# FF0881SA1.net
KiCad netlist of a schematic drawn in EAGLE
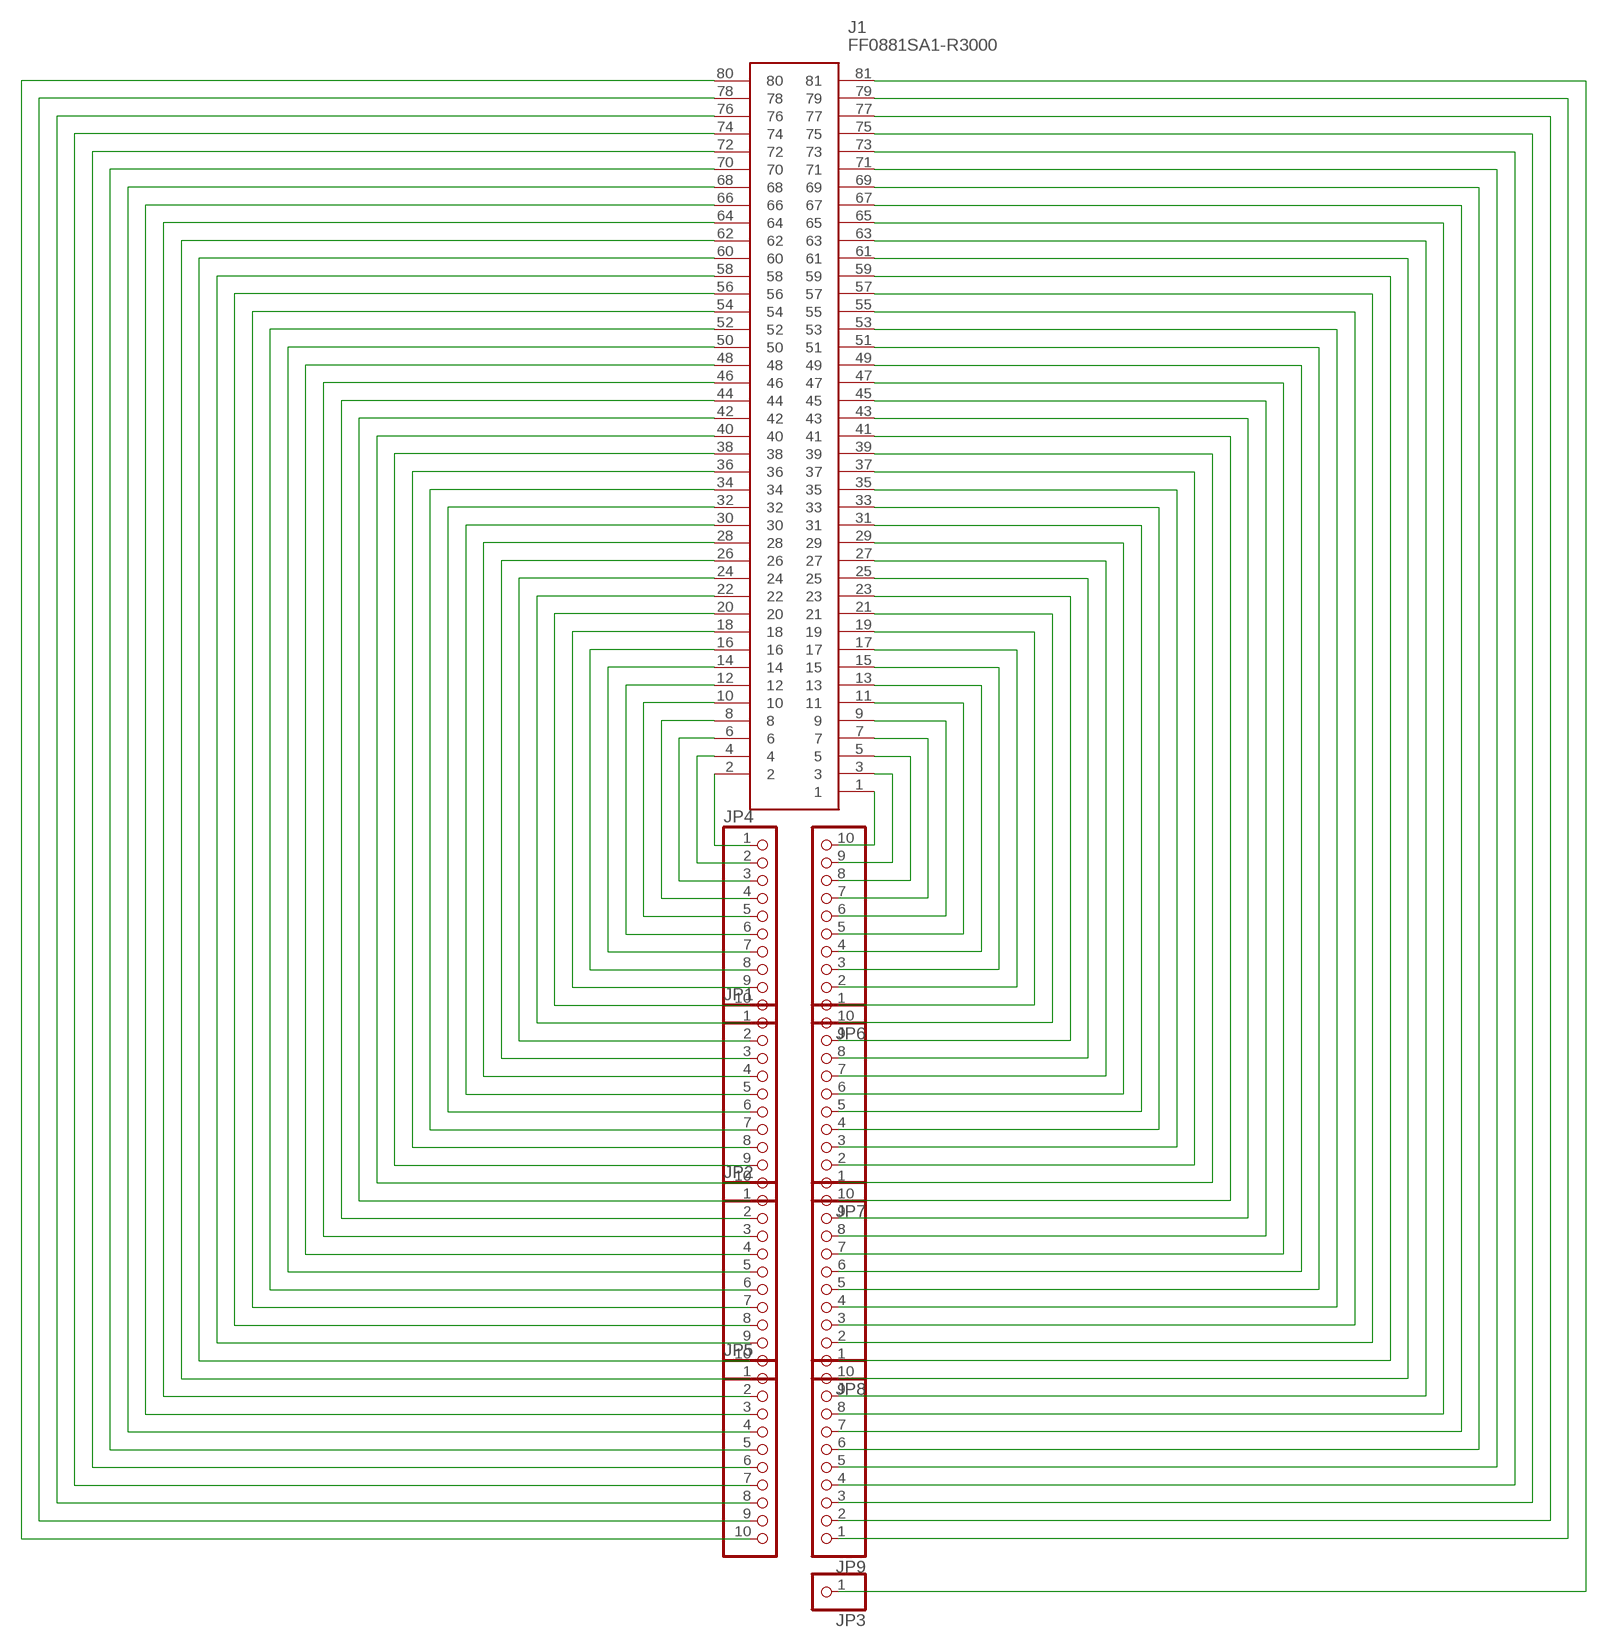
[diagram p0: schematic, sheet 1]

(export (version "E")
  (design (tool "Eeschema 10.0.6"))
  (components
    (comp (ref "J1")
      (value "FF0881SA1-R3000")
      (footprint "eagle-import:FF0881SA1R3000")
      (fields (field (name "MOUSER_PART_NUMBER") "656-FF0881SA1-R3000"))
      (libsource (lib "eagle-import") (part "FF0881SA1-R3000"))
    )
    (comp (ref "JP1")
      (value "PINHD-1X10")
      (footprint "eagle-import:1X10")
      (libsource (lib "eagle-import") (part "PINHD-1X10"))
    )
    (comp (ref "JP2")
      (value "PINHD-1X10")
      (footprint "eagle-import:1X10")
      (libsource (lib "eagle-import") (part "PINHD-1X10"))
    )
    (comp (ref "JP3")
      (value "PINHD-1X1")
      (footprint "eagle-import:1X01")
      (libsource (lib "eagle-import") (part "PINHD-1X1"))
    )
    (comp (ref "JP4")
      (value "PINHD-1X10")
      (footprint "eagle-import:1X10")
      (libsource (lib "eagle-import") (part "PINHD-1X10"))
    )
    (comp (ref "JP5")
      (value "PINHD-1X10")
      (footprint "eagle-import:1X10")
      (libsource (lib "eagle-import") (part "PINHD-1X10"))
    )
    (comp (ref "JP6")
      (value "PINHD-1X10")
      (footprint "eagle-import:1X10")
      (libsource (lib "eagle-import") (part "PINHD-1X10"))
    )
    (comp (ref "JP7")
      (value "PINHD-1X10")
      (footprint "eagle-import:1X10")
      (libsource (lib "eagle-import") (part "PINHD-1X10"))
    )
    (comp (ref "JP8")
      (value "PINHD-1X10")
      (footprint "eagle-import:1X10")
      (libsource (lib "eagle-import") (part "PINHD-1X10"))
    )
    (comp (ref "JP9")
      (value "PINHD-1X10")
      (footprint "eagle-import:1X10")
      (libsource (lib "eagle-import") (part "PINHD-1X10"))
    )
  )
  (nets
    (net (code "1") (name "Net-(J1-Pad1)") (class "Default")
      (node (ref "J1") (pin "1") (pinfunction "1_1") (pintype "bidirectional"))
      (node (ref "JP6") (pin "10") (pinfunction "10_10") (pintype "passive"))
    )
    (net (code "2") (name "Net-(J1-Pad2)") (class "Default")
      (node (ref "J1") (pin "2") (pinfunction "2_2") (pintype "bidirectional"))
      (node (ref "JP4") (pin "1") (pinfunction "1_1") (pintype "passive"))
    )
    (net (code "3") (name "Net-(J1-Pad3)") (class "Default")
      (node (ref "J1") (pin "3") (pinfunction "3_3") (pintype "bidirectional"))
      (node (ref "JP6") (pin "9") (pinfunction "9_9") (pintype "passive"))
    )
    (net (code "4") (name "Net-(J1-Pad4)") (class "Default")
      (node (ref "J1") (pin "4") (pinfunction "4_4") (pintype "bidirectional"))
      (node (ref "JP4") (pin "2") (pinfunction "2_2") (pintype "passive"))
    )
    (net (code "5") (name "Net-(J1-Pad5)") (class "Default")
      (node (ref "J1") (pin "5") (pinfunction "5_5") (pintype "bidirectional"))
      (node (ref "JP6") (pin "8") (pinfunction "8_8") (pintype "passive"))
    )
    (net (code "6") (name "Net-(J1-Pad6)") (class "Default")
      (node (ref "J1") (pin "6") (pinfunction "6_6") (pintype "bidirectional"))
      (node (ref "JP4") (pin "3") (pinfunction "3_3") (pintype "passive"))
    )
    (net (code "7") (name "Net-(J1-Pad7)") (class "Default")
      (node (ref "J1") (pin "7") (pinfunction "7_7") (pintype "bidirectional"))
      (node (ref "JP6") (pin "7") (pinfunction "7_7") (pintype "passive"))
    )
    (net (code "8") (name "Net-(J1-Pad8)") (class "Default")
      (node (ref "J1") (pin "8") (pinfunction "8_8") (pintype "bidirectional"))
      (node (ref "JP4") (pin "4") (pinfunction "4_4") (pintype "passive"))
    )
    (net (code "9") (name "Net-(J1-Pad9)") (class "Default")
      (node (ref "J1") (pin "9") (pinfunction "9_9") (pintype "bidirectional"))
      (node (ref "JP6") (pin "6") (pinfunction "6_6") (pintype "passive"))
    )
    (net (code "10") (name "Net-(J1-Pad10)") (class "Default")
      (node (ref "J1") (pin "10") (pinfunction "10_10") (pintype "bidirectional"))
      (node (ref "JP4") (pin "5") (pinfunction "5_5") (pintype "passive"))
    )
    (net (code "11") (name "Net-(J1-Pad11)") (class "Default")
      (node (ref "J1") (pin "11") (pinfunction "11_11") (pintype "bidirectional"))
      (node (ref "JP6") (pin "5") (pinfunction "5_5") (pintype "passive"))
    )
    (net (code "12") (name "Net-(J1-Pad12)") (class "Default")
      (node (ref "J1") (pin "12") (pinfunction "12_12") (pintype "bidirectional"))
      (node (ref "JP4") (pin "6") (pinfunction "6_6") (pintype "passive"))
    )
    (net (code "13") (name "Net-(J1-Pad13)") (class "Default")
      (node (ref "J1") (pin "13") (pinfunction "13_13") (pintype "bidirectional"))
      (node (ref "JP6") (pin "4") (pinfunction "4_4") (pintype "passive"))
    )
    (net (code "14") (name "Net-(J1-Pad14)") (class "Default")
      (node (ref "J1") (pin "14") (pinfunction "14_14") (pintype "bidirectional"))
      (node (ref "JP4") (pin "7") (pinfunction "7_7") (pintype "passive"))
    )
    (net (code "15") (name "Net-(J1-Pad15)") (class "Default")
      (node (ref "J1") (pin "15") (pinfunction "15_15") (pintype "bidirectional"))
      (node (ref "JP6") (pin "3") (pinfunction "3_3") (pintype "passive"))
    )
    (net (code "16") (name "Net-(J1-Pad16)") (class "Default")
      (node (ref "J1") (pin "16") (pinfunction "16_16") (pintype "bidirectional"))
      (node (ref "JP4") (pin "8") (pinfunction "8_8") (pintype "passive"))
    )
    (net (code "17") (name "Net-(J1-Pad17)") (class "Default")
      (node (ref "J1") (pin "17") (pinfunction "17_17") (pintype "bidirectional"))
      (node (ref "JP6") (pin "2") (pinfunction "2_2") (pintype "passive"))
    )
    (net (code "18") (name "Net-(J1-Pad18)") (class "Default")
      (node (ref "J1") (pin "18") (pinfunction "18_18") (pintype "bidirectional"))
      (node (ref "JP4") (pin "9") (pinfunction "9_9") (pintype "passive"))
    )
    (net (code "19") (name "Net-(J1-Pad19)") (class "Default")
      (node (ref "J1") (pin "19") (pinfunction "19_19") (pintype "bidirectional"))
      (node (ref "JP6") (pin "1") (pinfunction "1_1") (pintype "passive"))
    )
    (net (code "20") (name "Net-(J1-Pad20)") (class "Default")
      (node (ref "J1") (pin "20") (pinfunction "20_20") (pintype "bidirectional"))
      (node (ref "JP4") (pin "10") (pinfunction "10_10") (pintype "passive"))
    )
    (net (code "21") (name "Net-(J1-Pad21)") (class "Default")
      (node (ref "J1") (pin "21") (pinfunction "21_21") (pintype "bidirectional"))
      (node (ref "JP7") (pin "10") (pinfunction "10_10") (pintype "passive"))
    )
    (net (code "22") (name "Net-(J1-Pad22)") (class "Default")
      (node (ref "J1") (pin "22") (pinfunction "22_22") (pintype "bidirectional"))
      (node (ref "JP1") (pin "1") (pinfunction "1_1") (pintype "passive"))
    )
    (net (code "23") (name "Net-(J1-Pad23)") (class "Default")
      (node (ref "J1") (pin "23") (pinfunction "23_23") (pintype "bidirectional"))
      (node (ref "JP7") (pin "9") (pinfunction "9_9") (pintype "passive"))
    )
    (net (code "24") (name "Net-(J1-Pad24)") (class "Default")
      (node (ref "J1") (pin "24") (pinfunction "24_24") (pintype "bidirectional"))
      (node (ref "JP1") (pin "2") (pinfunction "2_2") (pintype "passive"))
    )
    (net (code "25") (name "Net-(J1-Pad25)") (class "Default")
      (node (ref "J1") (pin "25") (pinfunction "25_25") (pintype "bidirectional"))
      (node (ref "JP7") (pin "8") (pinfunction "8_8") (pintype "passive"))
    )
    (net (code "26") (name "Net-(J1-Pad26)") (class "Default")
      (node (ref "J1") (pin "26") (pinfunction "26_26") (pintype "bidirectional"))
      (node (ref "JP1") (pin "3") (pinfunction "3_3") (pintype "passive"))
    )
    (net (code "27") (name "Net-(J1-Pad27)") (class "Default")
      (node (ref "J1") (pin "27") (pinfunction "27_27") (pintype "bidirectional"))
      (node (ref "JP7") (pin "7") (pinfunction "7_7") (pintype "passive"))
    )
    (net (code "28") (name "Net-(J1-Pad28)") (class "Default")
      (node (ref "J1") (pin "28") (pinfunction "28_28") (pintype "bidirectional"))
      (node (ref "JP1") (pin "4") (pinfunction "4_4") (pintype "passive"))
    )
    (net (code "29") (name "Net-(J1-Pad29)") (class "Default")
      (node (ref "J1") (pin "29") (pinfunction "29_29") (pintype "bidirectional"))
      (node (ref "JP7") (pin "6") (pinfunction "6_6") (pintype "passive"))
    )
    (net (code "30") (name "Net-(J1-Pad30)") (class "Default")
      (node (ref "J1") (pin "30") (pinfunction "30_30") (pintype "bidirectional"))
      (node (ref "JP1") (pin "5") (pinfunction "5_5") (pintype "passive"))
    )
    (net (code "31") (name "Net-(J1-Pad31)") (class "Default")
      (node (ref "J1") (pin "31") (pinfunction "31_31") (pintype "bidirectional"))
      (node (ref "JP7") (pin "5") (pinfunction "5_5") (pintype "passive"))
    )
    (net (code "32") (name "Net-(J1-Pad32)") (class "Default")
      (node (ref "J1") (pin "32") (pinfunction "32_32") (pintype "bidirectional"))
      (node (ref "JP1") (pin "6") (pinfunction "6_6") (pintype "passive"))
    )
    (net (code "33") (name "Net-(J1-Pad33)") (class "Default")
      (node (ref "J1") (pin "33") (pinfunction "33_33") (pintype "bidirectional"))
      (node (ref "JP7") (pin "4") (pinfunction "4_4") (pintype "passive"))
    )
    (net (code "34") (name "Net-(J1-Pad34)") (class "Default")
      (node (ref "J1") (pin "34") (pinfunction "34_34") (pintype "bidirectional"))
      (node (ref "JP1") (pin "7") (pinfunction "7_7") (pintype "passive"))
    )
    (net (code "35") (name "Net-(J1-Pad35)") (class "Default")
      (node (ref "J1") (pin "35") (pinfunction "35_35") (pintype "bidirectional"))
      (node (ref "JP7") (pin "3") (pinfunction "3_3") (pintype "passive"))
    )
    (net (code "36") (name "Net-(J1-Pad36)") (class "Default")
      (node (ref "J1") (pin "36") (pinfunction "36_36") (pintype "bidirectional"))
      (node (ref "JP1") (pin "8") (pinfunction "8_8") (pintype "passive"))
    )
    (net (code "37") (name "Net-(J1-Pad37)") (class "Default")
      (node (ref "J1") (pin "37") (pinfunction "37_37") (pintype "bidirectional"))
      (node (ref "JP7") (pin "2") (pinfunction "2_2") (pintype "passive"))
    )
    (net (code "38") (name "Net-(J1-Pad38)") (class "Default")
      (node (ref "J1") (pin "38") (pinfunction "38_38") (pintype "bidirectional"))
      (node (ref "JP1") (pin "9") (pinfunction "9_9") (pintype "passive"))
    )
    (net (code "39") (name "Net-(J1-Pad39)") (class "Default")
      (node (ref "J1") (pin "39") (pinfunction "39_39") (pintype "bidirectional"))
      (node (ref "JP7") (pin "1") (pinfunction "1_1") (pintype "passive"))
    )
    (net (code "40") (name "Net-(J1-Pad40)") (class "Default")
      (node (ref "J1") (pin "40") (pinfunction "40_40") (pintype "bidirectional"))
      (node (ref "JP1") (pin "10") (pinfunction "10_10") (pintype "passive"))
    )
    (net (code "41") (name "Net-(J1-Pad41)") (class "Default")
      (node (ref "J1") (pin "41") (pinfunction "41_41") (pintype "bidirectional"))
      (node (ref "JP8") (pin "10") (pinfunction "10_10") (pintype "passive"))
    )
    (net (code "42") (name "Net-(J1-Pad42)") (class "Default")
      (node (ref "J1") (pin "42") (pinfunction "42_42") (pintype "bidirectional"))
      (node (ref "JP2") (pin "1") (pinfunction "1_1") (pintype "passive"))
    )
    (net (code "43") (name "Net-(J1-Pad43)") (class "Default")
      (node (ref "J1") (pin "43") (pinfunction "43_43") (pintype "bidirectional"))
      (node (ref "JP8") (pin "9") (pinfunction "9_9") (pintype "passive"))
    )
    (net (code "44") (name "Net-(J1-Pad44)") (class "Default")
      (node (ref "J1") (pin "44") (pinfunction "44_44") (pintype "bidirectional"))
      (node (ref "JP2") (pin "2") (pinfunction "2_2") (pintype "passive"))
    )
    (net (code "45") (name "Net-(J1-Pad45)") (class "Default")
      (node (ref "J1") (pin "45") (pinfunction "45_45") (pintype "bidirectional"))
      (node (ref "JP8") (pin "8") (pinfunction "8_8") (pintype "passive"))
    )
    (net (code "46") (name "Net-(J1-Pad46)") (class "Default")
      (node (ref "J1") (pin "46") (pinfunction "46_46") (pintype "bidirectional"))
      (node (ref "JP2") (pin "3") (pinfunction "3_3") (pintype "passive"))
    )
    (net (code "47") (name "Net-(J1-Pad47)") (class "Default")
      (node (ref "J1") (pin "47") (pinfunction "47_47") (pintype "bidirectional"))
      (node (ref "JP8") (pin "7") (pinfunction "7_7") (pintype "passive"))
    )
    (net (code "48") (name "Net-(J1-Pad48)") (class "Default")
      (node (ref "J1") (pin "48") (pinfunction "48_48") (pintype "bidirectional"))
      (node (ref "JP2") (pin "4") (pinfunction "4_4") (pintype "passive"))
    )
    (net (code "49") (name "Net-(J1-Pad49)") (class "Default")
      (node (ref "J1") (pin "49") (pinfunction "49_49") (pintype "bidirectional"))
      (node (ref "JP8") (pin "6") (pinfunction "6_6") (pintype "passive"))
    )
    (net (code "50") (name "Net-(J1-Pad50)") (class "Default")
      (node (ref "J1") (pin "50") (pinfunction "50_50") (pintype "bidirectional"))
      (node (ref "JP2") (pin "5") (pinfunction "5_5") (pintype "passive"))
    )
    (net (code "51") (name "Net-(J1-Pad51)") (class "Default")
      (node (ref "J1") (pin "51") (pinfunction "51_51") (pintype "bidirectional"))
      (node (ref "JP8") (pin "5") (pinfunction "5_5") (pintype "passive"))
    )
    (net (code "52") (name "Net-(J1-Pad52)") (class "Default")
      (node (ref "J1") (pin "52") (pinfunction "52_52") (pintype "bidirectional"))
      (node (ref "JP2") (pin "6") (pinfunction "6_6") (pintype "passive"))
    )
    (net (code "53") (name "Net-(J1-Pad53)") (class "Default")
      (node (ref "J1") (pin "53") (pinfunction "53_53") (pintype "bidirectional"))
      (node (ref "JP8") (pin "4") (pinfunction "4_4") (pintype "passive"))
    )
    (net (code "54") (name "Net-(J1-Pad54)") (class "Default")
      (node (ref "J1") (pin "54") (pinfunction "54_54") (pintype "bidirectional"))
      (node (ref "JP2") (pin "7") (pinfunction "7_7") (pintype "passive"))
    )
    (net (code "55") (name "Net-(J1-Pad55)") (class "Default")
      (node (ref "J1") (pin "55") (pinfunction "55_55") (pintype "bidirectional"))
      (node (ref "JP8") (pin "3") (pinfunction "3_3") (pintype "passive"))
    )
    (net (code "56") (name "Net-(J1-Pad56)") (class "Default")
      (node (ref "J1") (pin "56") (pinfunction "56_56") (pintype "bidirectional"))
      (node (ref "JP2") (pin "8") (pinfunction "8_8") (pintype "passive"))
    )
    (net (code "57") (name "Net-(J1-Pad57)") (class "Default")
      (node (ref "J1") (pin "57") (pinfunction "57_57") (pintype "bidirectional"))
      (node (ref "JP8") (pin "2") (pinfunction "2_2") (pintype "passive"))
    )
    (net (code "58") (name "Net-(J1-Pad58)") (class "Default")
      (node (ref "J1") (pin "58") (pinfunction "58_58") (pintype "bidirectional"))
      (node (ref "JP2") (pin "9") (pinfunction "9_9") (pintype "passive"))
    )
    (net (code "59") (name "Net-(J1-Pad59)") (class "Default")
      (node (ref "J1") (pin "59") (pinfunction "59_59") (pintype "bidirectional"))
      (node (ref "JP8") (pin "1") (pinfunction "1_1") (pintype "passive"))
    )
    (net (code "60") (name "Net-(J1-Pad60)") (class "Default")
      (node (ref "J1") (pin "60") (pinfunction "60_60") (pintype "bidirectional"))
      (node (ref "JP2") (pin "10") (pinfunction "10_10") (pintype "passive"))
    )
    (net (code "61") (name "Net-(J1-Pad61)") (class "Default")
      (node (ref "J1") (pin "61") (pinfunction "61_61") (pintype "bidirectional"))
      (node (ref "JP9") (pin "10") (pinfunction "10_10") (pintype "passive"))
    )
    (net (code "62") (name "Net-(J1-Pad62)") (class "Default")
      (node (ref "J1") (pin "62") (pinfunction "62_62") (pintype "bidirectional"))
      (node (ref "JP5") (pin "1") (pinfunction "1_1") (pintype "passive"))
    )
    (net (code "63") (name "Net-(J1-Pad63)") (class "Default")
      (node (ref "J1") (pin "63") (pinfunction "63_63") (pintype "bidirectional"))
      (node (ref "JP9") (pin "9") (pinfunction "9_9") (pintype "passive"))
    )
    (net (code "64") (name "Net-(J1-Pad64)") (class "Default")
      (node (ref "J1") (pin "64") (pinfunction "64_64") (pintype "bidirectional"))
      (node (ref "JP5") (pin "2") (pinfunction "2_2") (pintype "passive"))
    )
    (net (code "65") (name "Net-(J1-Pad65)") (class "Default")
      (node (ref "J1") (pin "65") (pinfunction "65_65") (pintype "bidirectional"))
      (node (ref "JP9") (pin "8") (pinfunction "8_8") (pintype "passive"))
    )
    (net (code "66") (name "Net-(J1-Pad66)") (class "Default")
      (node (ref "J1") (pin "66") (pinfunction "66_66") (pintype "bidirectional"))
      (node (ref "JP5") (pin "3") (pinfunction "3_3") (pintype "passive"))
    )
    (net (code "67") (name "Net-(J1-Pad67)") (class "Default")
      (node (ref "J1") (pin "67") (pinfunction "67_67") (pintype "bidirectional"))
      (node (ref "JP9") (pin "7") (pinfunction "7_7") (pintype "passive"))
    )
    (net (code "68") (name "Net-(J1-Pad68)") (class "Default")
      (node (ref "J1") (pin "68") (pinfunction "68_68") (pintype "bidirectional"))
      (node (ref "JP5") (pin "4") (pinfunction "4_4") (pintype "passive"))
    )
    (net (code "69") (name "Net-(J1-Pad69)") (class "Default")
      (node (ref "J1") (pin "69") (pinfunction "69_69") (pintype "bidirectional"))
      (node (ref "JP9") (pin "6") (pinfunction "6_6") (pintype "passive"))
    )
    (net (code "70") (name "Net-(J1-Pad70)") (class "Default")
      (node (ref "J1") (pin "70") (pinfunction "70_70") (pintype "bidirectional"))
      (node (ref "JP5") (pin "5") (pinfunction "5_5") (pintype "passive"))
    )
    (net (code "71") (name "Net-(J1-Pad71)") (class "Default")
      (node (ref "J1") (pin "71") (pinfunction "71_71") (pintype "bidirectional"))
      (node (ref "JP9") (pin "5") (pinfunction "5_5") (pintype "passive"))
    )
    (net (code "72") (name "Net-(J1-Pad72)") (class "Default")
      (node (ref "J1") (pin "72") (pinfunction "72_72") (pintype "bidirectional"))
      (node (ref "JP5") (pin "6") (pinfunction "6_6") (pintype "passive"))
    )
    (net (code "73") (name "Net-(J1-Pad73)") (class "Default")
      (node (ref "J1") (pin "73") (pinfunction "73_73") (pintype "bidirectional"))
      (node (ref "JP9") (pin "4") (pinfunction "4_4") (pintype "passive"))
    )
    (net (code "74") (name "Net-(J1-Pad74)") (class "Default")
      (node (ref "J1") (pin "74") (pinfunction "74_74") (pintype "bidirectional"))
      (node (ref "JP5") (pin "7") (pinfunction "7_7") (pintype "passive"))
    )
    (net (code "75") (name "Net-(J1-Pad75)") (class "Default")
      (node (ref "J1") (pin "75") (pinfunction "75_75") (pintype "bidirectional"))
      (node (ref "JP9") (pin "3") (pinfunction "3_3") (pintype "passive"))
    )
    (net (code "76") (name "Net-(J1-Pad76)") (class "Default")
      (node (ref "J1") (pin "76") (pinfunction "76_76") (pintype "bidirectional"))
      (node (ref "JP5") (pin "8") (pinfunction "8_8") (pintype "passive"))
    )
    (net (code "77") (name "Net-(J1-Pad77)") (class "Default")
      (node (ref "J1") (pin "77") (pinfunction "77_77") (pintype "bidirectional"))
      (node (ref "JP9") (pin "2") (pinfunction "2_2") (pintype "passive"))
    )
    (net (code "78") (name "Net-(J1-Pad78)") (class "Default")
      (node (ref "J1") (pin "78") (pinfunction "78_78") (pintype "bidirectional"))
      (node (ref "JP5") (pin "9") (pinfunction "9_9") (pintype "passive"))
    )
    (net (code "79") (name "Net-(J1-Pad79)") (class "Default")
      (node (ref "J1") (pin "79") (pinfunction "79_79") (pintype "bidirectional"))
      (node (ref "JP9") (pin "1") (pinfunction "1_1") (pintype "passive"))
    )
    (net (code "80") (name "Net-(J1-Pad80)") (class "Default")
      (node (ref "J1") (pin "80") (pinfunction "80_80") (pintype "bidirectional"))
      (node (ref "JP5") (pin "10") (pinfunction "10_10") (pintype "passive"))
    )
    (net (code "81") (name "Net-(J1-Pad81)") (class "Default")
      (node (ref "J1") (pin "81") (pinfunction "81_81") (pintype "bidirectional"))
      (node (ref "JP3") (pin "1") (pinfunction "1_1") (pintype "passive"))
    )
  )
)
